# baskettarget_V1.net
KiCad netlist of a schematic drawn in EAGLE
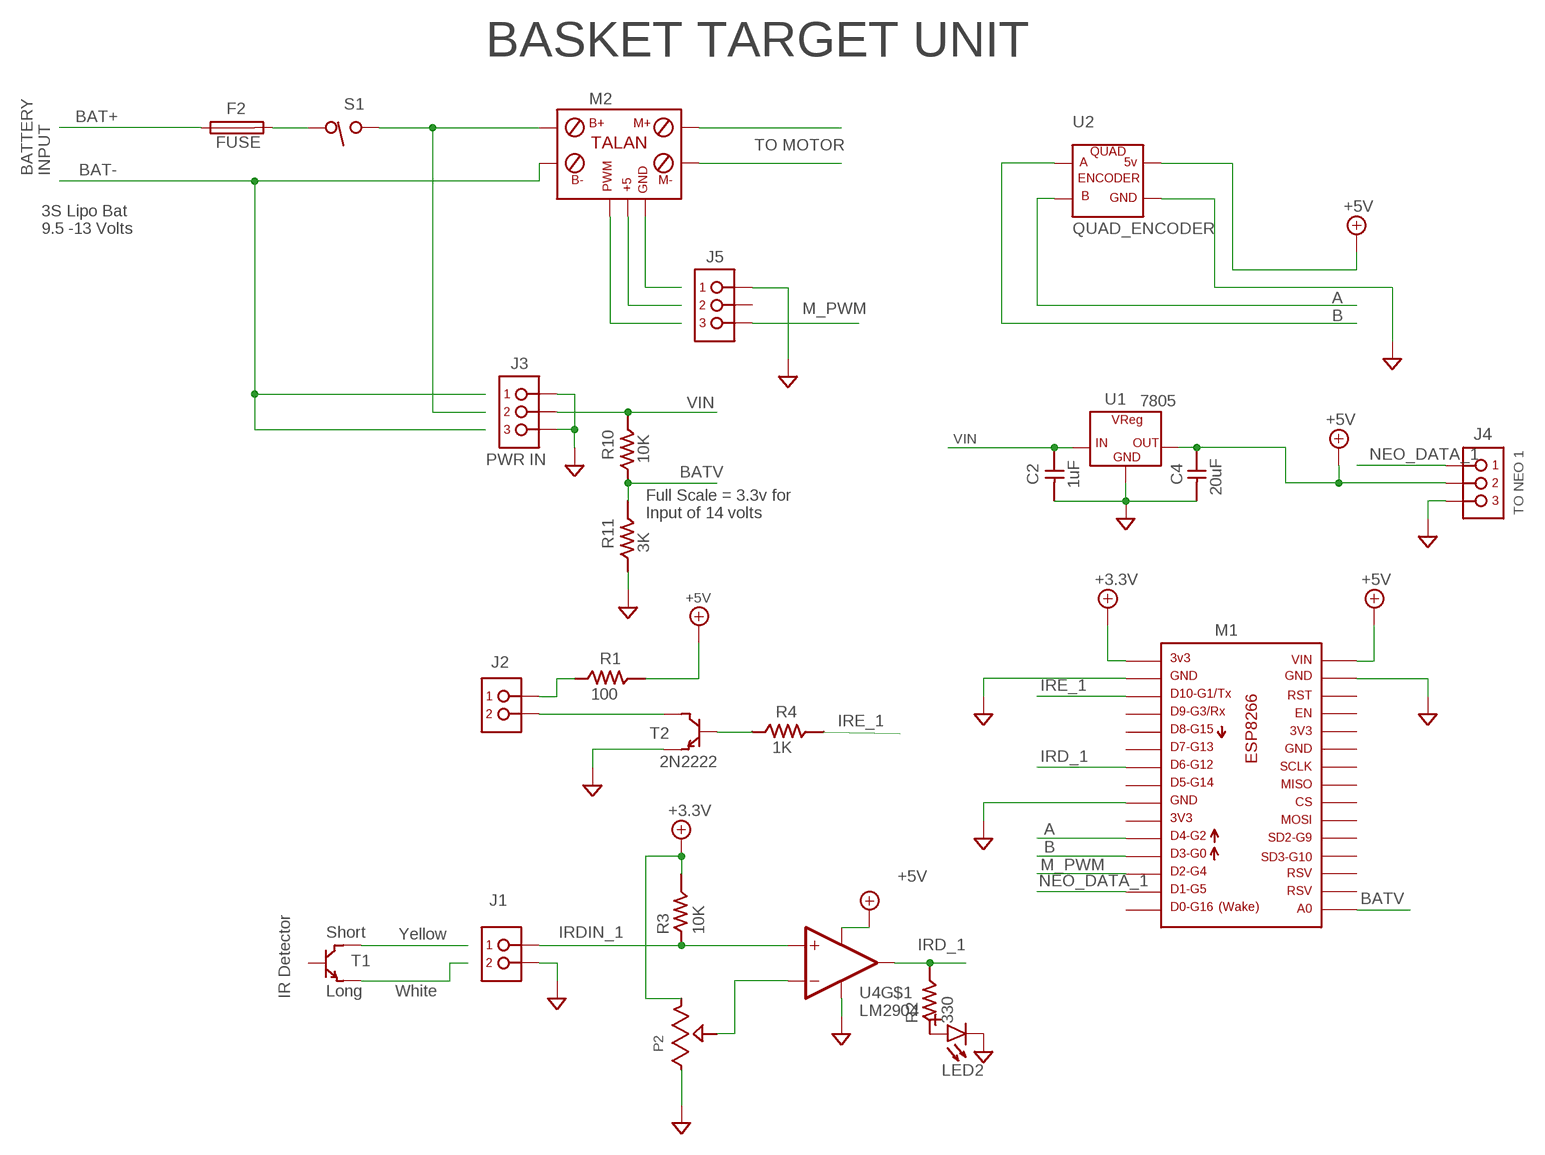
[diagram p0: schematic, sheet 1]

(export (version "E")
  (design (tool "Eeschema 10.0.6"))
  (components
    (comp (ref "C2")
      (value "1uF")
      (footprint "eagle-import:CAP200")
      (libsource (lib "eagle-import") (part "CAP200"))
    )
    (comp (ref "C4")
      (value "20uF")
      (footprint "eagle-import:CAP200")
      (libsource (lib "eagle-import") (part "CAP200"))
    )
    (comp (ref "F2")
      (value "FUSE")
      (footprint "eagle-import:FUSE_HOLDER_WICKMANN-19596")
      (libsource (lib "eagle-import") (part "FUSE19596"))
    )
    (comp (ref "J1")
      (value "PINHDR_1X2-JST")
      (footprint "eagle-import:JST-XH_098_VERT_1X2")
      (libsource (lib "eagle-import") (part "PINHDR_1X2-JST"))
    )
    (comp (ref "J2")
      (value "PINHDR_1X2-JST")
      (footprint "eagle-import:JST-XH_098_VERT_1X2")
      (libsource (lib "eagle-import") (part "PINHDR_1X2-JST"))
    )
    (comp (ref "J3")
      (value "PINHDR_1X3XH-JST")
      (footprint "eagle-import:JST-XH_098_VERT_1X3")
      (libsource (lib "eagle-import") (part "PINHDR_1X3-JSTXH"))
    )
    (comp (ref "J4")
      (value "PINHDR_1X3XH-JST")
      (footprint "eagle-import:JST-XH_098_VERT_1X3")
      (libsource (lib "eagle-import") (part "PINHDR_1X3-JSTXH"))
    )
    (comp (ref "J5")
      (value "PINHDR_1X3XH-JST")
      (footprint "eagle-import:JST-XH_098_VERT_1X3")
      (libsource (lib "eagle-import") (part "PINHDR_1X3-JSTXH"))
    )
    (comp (ref "LED2")
      (value "LEDTH-DIP-100")
      (footprint "eagle-import:LED-TH100")
      (libsource (lib "eagle-import") (part "LEDTH-DIP-100"))
    )
    (comp (ref "M1")
      (value "ESP8266_MODULE")
      (footprint "eagle-import:ESP8266_MODULE")
      (libsource (lib "eagle-import") (part "ESP8266_MODULE"))
    )
    (comp (ref "M2")
      (value "TALAN")
      (footprint "eagle-import:TALAN_PWM")
      (libsource (lib "eagle-import") (part "TALAN"))
    )
    (comp (ref "P2")
      (value "TRIMPOT-SIP")
      (footprint "eagle-import:TRIMPOT_SIP_100")
      (libsource (lib "eagle-import") (part "TRIMPOT-SIP"))
    )
    (comp (ref "R1")
      (value "100")
      (footprint "eagle-import:R300")
      (libsource (lib "eagle-import") (part "RTHOLE300"))
    )
    (comp (ref "R2")
      (value "330")
      (footprint "eagle-import:R300")
      (libsource (lib "eagle-import") (part "RTHOLE300"))
    )
    (comp (ref "R3")
      (value "10K")
      (footprint "eagle-import:R300")
      (libsource (lib "eagle-import") (part "RTHOLE300"))
    )
    (comp (ref "R4")
      (value "1K")
      (footprint "eagle-import:R300")
      (libsource (lib "eagle-import") (part "RTHOLE300"))
    )
    (comp (ref "R10")
      (value "10K")
      (footprint "eagle-import:R300")
      (libsource (lib "eagle-import") (part "RTHOLE300"))
    )
    (comp (ref "R11")
      (value "3K")
      (footprint "eagle-import:R300")
      (libsource (lib "eagle-import") (part "RTHOLE300"))
    )
    (comp (ref "S1")
      (value "TOGGLE_SWITCH_SPST")
      (footprint "eagle-import:SPST_TOGGLE")
      (libsource (lib "eagle-import") (part "TOGGLE_SWITCH_SPST"))
    )
    (comp (ref "T1")
      (value "T_NPN")
      (footprint "eagle-import:TO-92")
      (libsource (lib "eagle-import") (part "T_NPN"))
    )
    (comp (ref "T2")
      (value "2N2222")
      (footprint "eagle-import:TO-92")
      (libsource (lib "eagle-import") (part "T_NPN"))
    )
    (comp (ref "U1")
      (value "7805")
      (footprint "eagle-import:PINHDR_TH_100_1X3")
      (libsource (lib "eagle-import") (part "VREG-3-DIP"))
    )
    (comp (ref "U2")
      (value "QUAD_ENCODER")
      (footprint "eagle-import:QUAD_ENCODER")
      (libsource (lib "eagle-import") (part "QUAD_ENCODER"))
    )
    (comp (ref "U4")
      (value "LM2904")
      (footprint "eagle-import:DIP8")
      (libsource (lib "eagle-import") (part "LM2904"))
    )
  )
  (nets
    (net (code "1") (name "+3.3V") (class "Default")
      (node (ref "M1") (pin "P$1") (pinfunction "P$1_P$1") (pintype "passive"))
      (node (ref "P2") (pin "P$3") (pinfunction "P$3_P$3") (pintype "passive"))
      (node (ref "R3") (pin "P$2") (pinfunction "2_P$2") (pintype "passive"))
    )
    (net (code "2") (name "+5V") (class "Default")
      (node (ref "C4") (pin "2") (pinfunction "2_2") (pintype "passive"))
      (node (ref "J4") (pin "2") (pinfunction "2_2") (pintype "passive"))
      (node (ref "M1") (pin "P$30") (pinfunction "P$30_P$30") (pintype "passive"))
      (node (ref "R1") (pin "P$2") (pinfunction "2_P$2") (pintype "passive"))
      (node (ref "U1") (pin "3") (pinfunction "OUT_3") (pintype "passive"))
      (node (ref "U2") (pin "5V") (pinfunction "5V_5V") (pintype "passive"))
      (node (ref "U4") (pin "P$8") (pinfunction "P+_P$8") (pintype "passive"))
    )
    (net (code "3") (name "/A") (class "Default")
      (node (ref "M1") (pin "P$11") (pinfunction "P$11_P$11") (pintype "passive"))
      (node (ref "U2") (pin "B") (pinfunction "B_B") (pintype "passive"))
    )
    (net (code "4") (name "/B") (class "Default")
      (node (ref "M1") (pin "P$12") (pinfunction "P$12_P$12") (pintype "passive"))
      (node (ref "U2") (pin "A") (pinfunction "A_A") (pintype "passive"))
    )
    (net (code "5") (name "/BAT+") (class "Default")
      (node (ref "F2") (pin "A") (pinfunction "1_A") (pintype "passive"))
    )
    (net (code "6") (name "/BAT-") (class "Default")
      (node (ref "M2") (pin "B-") (pinfunction "B-_B-") (pintype "passive"))
    )
    (net (code "7") (name "/BATV") (class "Default")
      (node (ref "M1") (pin "P$16") (pinfunction "P$16_P$16") (pintype "passive"))
      (node (ref "R10") (pin "P$1") (pinfunction "1_P$1") (pintype "passive"))
      (node (ref "R11") (pin "P$2") (pinfunction "2_P$2") (pintype "passive"))
    )
    (net (code "8") (name "/IRDIN_1") (class "Default")
      (node (ref "J1") (pin "1") (pinfunction "1_1") (pintype "passive"))
      (node (ref "R3") (pin "P$1") (pinfunction "1_P$1") (pintype "passive"))
      (node (ref "U4") (pin "P$3") (pinfunction "+IN_P$3") (pintype "input"))
    )
    (net (code "9") (name "/IRD_1") (class "Default")
      (node (ref "M1") (pin "P$7") (pinfunction "P$7_P$7") (pintype "passive"))
      (node (ref "R2") (pin "P$2") (pinfunction "2_P$2") (pintype "passive"))
      (node (ref "U4") (pin "P$1") (pinfunction "OUT_P$1") (pintype "output"))
    )
    (net (code "10") (name "/IRE_1") (class "Default")
      (node (ref "M1") (pin "P$3") (pinfunction "P$3_P$3") (pintype "passive"))
      (node (ref "R4") (pin "P$2") (pinfunction "2_P$2") (pintype "passive"))
    )
    (net (code "11") (name "/M_PWM") (class "Default")
      (node (ref "J5") (pin "1") (pinfunction "3_1") (pintype "passive"))
      (node (ref "M1") (pin "P$13") (pinfunction "P$13_P$13") (pintype "passive"))
    )
    (net (code "12") (name "/NEO_DATA_1") (class "Default")
      (node (ref "J4") (pin "3") (pinfunction "1_3") (pintype "passive"))
      (node (ref "M1") (pin "P$14") (pinfunction "P$14_P$14") (pintype "passive"))
    )
    (net (code "13") (name "/VIN") (class "Default")
      (node (ref "C2") (pin "2") (pinfunction "2_2") (pintype "passive"))
      (node (ref "J3") (pin "2") (pinfunction "2_2") (pintype "passive"))
      (node (ref "R10") (pin "P$2") (pinfunction "2_P$2") (pintype "passive"))
      (node (ref "U1") (pin "1") (pinfunction "IN_1") (pintype "passive"))
    )
    (net (code "14") (name "GND") (class "Default")
      (node (ref "C2") (pin "1") (pinfunction "1_1") (pintype "passive"))
      (node (ref "C4") (pin "1") (pinfunction "1_1") (pintype "passive"))
      (node (ref "J1") (pin "2") (pinfunction "2_2") (pintype "passive"))
      (node (ref "J3") (pin "1") (pinfunction "3_1") (pintype "passive"))
      (node (ref "J3") (pin "3") (pinfunction "1_3") (pintype "passive"))
      (node (ref "J4") (pin "1") (pinfunction "3_1") (pintype "passive"))
      (node (ref "J5") (pin "3") (pinfunction "1_3") (pintype "passive"))
      (node (ref "LED2") (pin "P$2") (pinfunction "CATHODE_P$2") (pintype "passive"))
      (node (ref "M1") (pin "P$2") (pinfunction "P$2_P$2") (pintype "passive"))
      (node (ref "M1") (pin "P$29") (pinfunction "P$29_P$29") (pintype "passive"))
      (node (ref "M1") (pin "P$9") (pinfunction "P$9_P$9") (pintype "passive"))
      (node (ref "P2") (pin "P$1") (pinfunction "P$1_P$1") (pintype "passive"))
      (node (ref "R11") (pin "P$1") (pinfunction "1_P$1") (pintype "passive"))
      (node (ref "T2") (pin "P$3") (pinfunction "EMITTER_P$3") (pintype "passive"))
      (node (ref "U1") (pin "2") (pinfunction "GND_2") (pintype "passive"))
      (node (ref "U2") (pin "GND") (pinfunction "GND_GND") (pintype "passive"))
      (node (ref "U4") (pin "P$4") (pinfunction "P-_P$4") (pintype "passive"))
    )
    (net (code "15") (name "Net-(F2-2)") (class "Default")
      (node (ref "F2") (pin "B") (pinfunction "2_B") (pintype "passive"))
      (node (ref "S1") (pin "P$1") (pinfunction "P$1_P$1") (pintype "passive"))
    )
    (net (code "16") (name "Net-(LED2-ANODE)") (class "Default")
      (node (ref "LED2") (pin "P$1") (pinfunction "ANODE_P$1") (pintype "passive"))
      (node (ref "R2") (pin "P$1") (pinfunction "1_P$1") (pintype "passive"))
    )
    (net (code "17") (name "Net-(M2-PadB+)") (class "Default")
      (node (ref "M2") (pin "B+") (pinfunction "B+_B+") (pintype "passive"))
      (node (ref "S1") (pin "P$3") (pinfunction "P$3_P$3") (pintype "passive"))
    )
    (net (code "18") (name "Net-(R1-1)") (class "Default")
      (node (ref "J2") (pin "1") (pinfunction "1_1") (pintype "passive"))
      (node (ref "R1") (pin "P$1") (pinfunction "1_P$1") (pintype "passive"))
    )
    (net (code "19") (name "Net-(R4-1)") (class "Default")
      (node (ref "R4") (pin "P$1") (pinfunction "1_P$1") (pintype "passive"))
      (node (ref "T2") (pin "P$2") (pinfunction "BASE_P$2") (pintype "passive"))
    )
    (net (code "20") (name "Net-(T2-COLLECTOR)") (class "Default")
      (node (ref "J2") (pin "2") (pinfunction "2_2") (pintype "passive"))
      (node (ref "T2") (pin "P$1") (pinfunction "COLLECTOR_P$1") (pintype "passive"))
    )
    (net (code "21") (name "Net-(U4A--IN)") (class "Default")
      (node (ref "P2") (pin "P$2") (pinfunction "P$2_P$2") (pintype "passive"))
      (node (ref "U4") (pin "P$2") (pinfunction "-IN_P$2") (pintype "input"))
    )
    (net (code "22") (name "unconnected-(J5-Pad2)") (class "Default")
      (node (ref "J5") (pin "2") (pinfunction "2_2") (pintype "passive"))
    )
    (net (code "23") (name "unconnected-(M1-PadP$4)") (class "Default")
      (node (ref "M1") (pin "P$4") (pinfunction "P$4_P$4") (pintype "passive"))
    )
    (net (code "24") (name "unconnected-(M1-PadP$5)") (class "Default")
      (node (ref "M1") (pin "P$5") (pinfunction "P$5_P$5") (pintype "passive"))
    )
    (net (code "25") (name "unconnected-(M1-PadP$6)") (class "Default")
      (node (ref "M1") (pin "P$6") (pinfunction "P$6_P$6") (pintype "passive"))
    )
    (net (code "26") (name "unconnected-(M1-PadP$8)") (class "Default")
      (node (ref "M1") (pin "P$8") (pinfunction "P$8_P$8") (pintype "passive"))
    )
    (net (code "27") (name "unconnected-(M1-PadP$10)") (class "Default")
      (node (ref "M1") (pin "P$10") (pinfunction "P$10_P$10") (pintype "passive"))
    )
    (net (code "28") (name "unconnected-(M1-PadP$15)") (class "Default")
      (node (ref "M1") (pin "P$15") (pinfunction "P$15_P$15") (pintype "passive"))
    )
    (net (code "29") (name "unconnected-(M1-PadP$17)") (class "Default")
      (node (ref "M1") (pin "P$17") (pinfunction "P$17_P$17") (pintype "passive"))
    )
    (net (code "30") (name "unconnected-(M1-PadP$18)") (class "Default")
      (node (ref "M1") (pin "P$18") (pinfunction "P$18_P$18") (pintype "passive"))
    )
    (net (code "31") (name "unconnected-(M1-PadP$19)") (class "Default")
      (node (ref "M1") (pin "P$19") (pinfunction "P$19_P$19") (pintype "passive"))
    )
    (net (code "32") (name "unconnected-(M1-PadP$20)") (class "Default")
      (node (ref "M1") (pin "P$20") (pinfunction "P$20_P$20") (pintype "passive"))
    )
    (net (code "33") (name "unconnected-(M1-PadP$21)") (class "Default")
      (node (ref "M1") (pin "P$21") (pinfunction "P$21_P$21") (pintype "passive"))
    )
    (net (code "34") (name "unconnected-(M1-PadP$22)") (class "Default")
      (node (ref "M1") (pin "P$22") (pinfunction "P$22_P$22") (pintype "passive"))
    )
    (net (code "35") (name "unconnected-(M1-PadP$23)") (class "Default")
      (node (ref "M1") (pin "P$23") (pinfunction "P$23_P$23") (pintype "passive"))
    )
    (net (code "36") (name "unconnected-(M1-PadP$24)") (class "Default")
      (node (ref "M1") (pin "P$24") (pinfunction "P$24_P$24") (pintype "passive"))
    )
    (net (code "37") (name "unconnected-(M1-PadP$25)") (class "Default")
      (node (ref "M1") (pin "P$25") (pinfunction "P$25_P$25") (pintype "passive"))
    )
    (net (code "38") (name "unconnected-(M1-PadP$26)") (class "Default")
      (node (ref "M1") (pin "P$26") (pinfunction "P$26_P$26") (pintype "passive"))
    )
    (net (code "39") (name "unconnected-(M1-PadP$27)") (class "Default")
      (node (ref "M1") (pin "P$27") (pinfunction "P$27_P$27") (pintype "passive"))
    )
    (net (code "40") (name "unconnected-(M1-PadP$28)") (class "Default")
      (node (ref "M1") (pin "P$28") (pinfunction "P$28_P$28") (pintype "passive"))
    )
    (net (code "41") (name "unconnected-(M2-Pad5V)") (class "Default")
      (node (ref "M2") (pin "5V") (pinfunction "5V_5V") (pintype "passive"))
    )
    (net (code "42") (name "unconnected-(M2-PadGND)") (class "Default")
      (node (ref "M2") (pin "GND") (pinfunction "GND_GND") (pintype "passive"))
    )
    (net (code "43") (name "unconnected-(M2-PadM+)") (class "Default")
      (node (ref "M2") (pin "M+") (pinfunction "M+_M+") (pintype "passive"))
    )
    (net (code "44") (name "unconnected-(M2-PadM-)") (class "Default")
      (node (ref "M2") (pin "M-") (pinfunction "M-_M-") (pintype "passive"))
    )
    (net (code "45") (name "unconnected-(M2-PadPWM)") (class "Default")
      (node (ref "M2") (pin "PWM") (pinfunction "PWM_PWM") (pintype "passive"))
    )
    (net (code "46") (name "unconnected-(S1-PadP$2)") (class "Default")
      (node (ref "S1") (pin "P$2") (pinfunction "P$2_P$2") (pintype "passive"))
    )
    (net (code "47") (name "unconnected-(T1-BASE-PadP$2)") (class "Default")
      (node (ref "T1") (pin "P$2") (pinfunction "BASE_P$2") (pintype "passive"))
    )
    (net (code "48") (name "unconnected-(T1-COLLECTOR-PadP$1)") (class "Default")
      (node (ref "T1") (pin "P$1") (pinfunction "COLLECTOR_P$1") (pintype "passive"))
    )
    (net (code "49") (name "unconnected-(T1-EMITTER-PadP$3)") (class "Default")
      (node (ref "T1") (pin "P$3") (pinfunction "EMITTER_P$3") (pintype "passive"))
    )
  )
)
